# PCB-E21-TVS.net
KiCad netlist of a schematic drawn in EAGLE
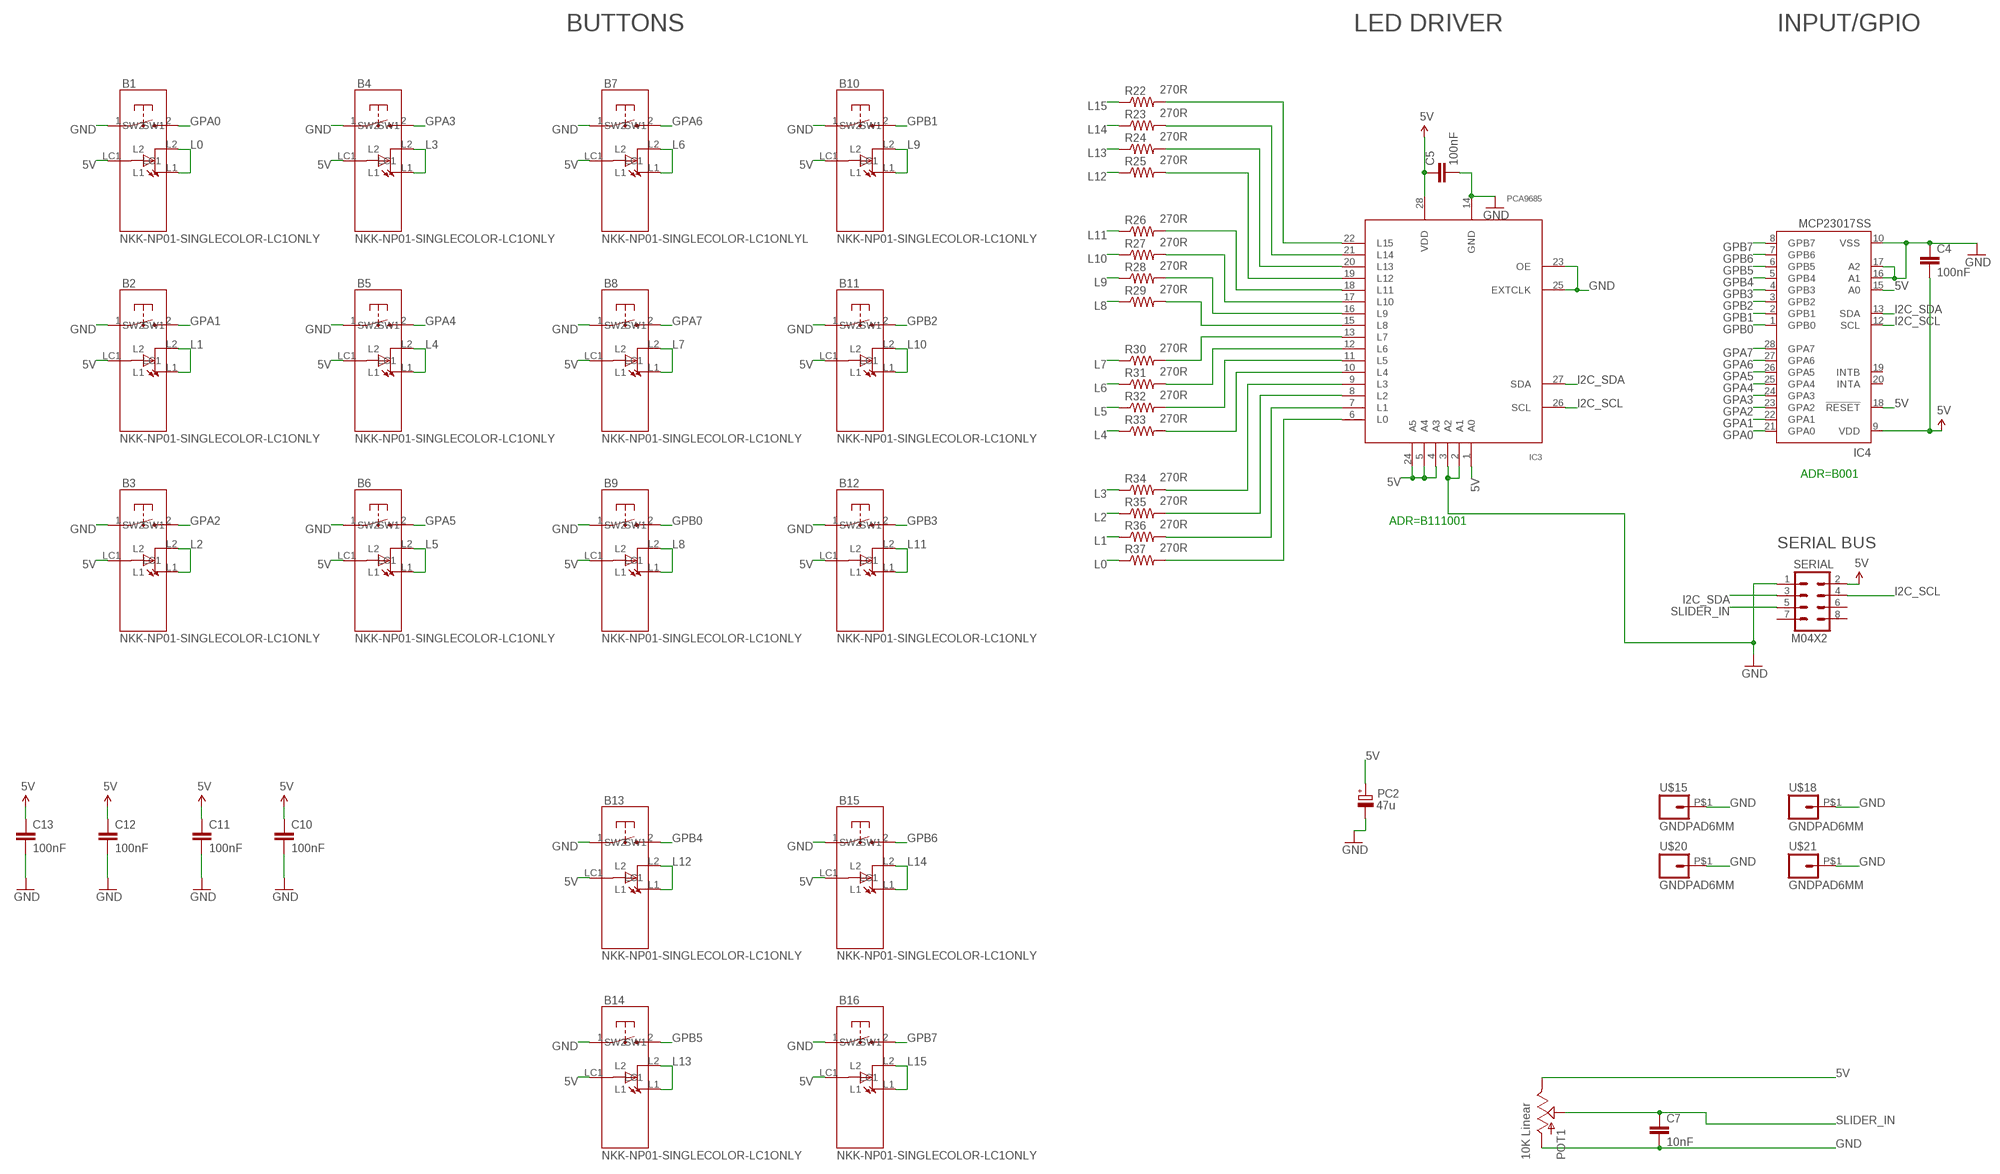
[diagram p0: schematic, sheet 1]

(export (version "E")
  (design (tool "Eeschema 10.0.6"))
  (components
    (comp (ref "B1")
      (value "NKK-NP01-SINGLECOLOR-LC1ONLY")
      (footprint "eagle-import:NKK-NP01_LESSHOLES2")
      (libsource (lib "eagle-import") (part "NKK-NP01-SINGLECOLOR-LC1ONLY"))
    )
    (comp (ref "B2")
      (value "NKK-NP01-SINGLECOLOR-LC1ONLY")
      (footprint "eagle-import:NKK-NP01_LESSHOLES2")
      (libsource (lib "eagle-import") (part "NKK-NP01-SINGLECOLOR-LC1ONLY"))
    )
    (comp (ref "B3")
      (value "NKK-NP01-SINGLECOLOR-LC1ONLY")
      (footprint "eagle-import:NKK-NP01_LESSHOLES2")
      (libsource (lib "eagle-import") (part "NKK-NP01-SINGLECOLOR-LC1ONLY"))
    )
    (comp (ref "B4")
      (value "NKK-NP01-SINGLECOLOR-LC1ONLY")
      (footprint "eagle-import:NKK-NP01_LESSHOLES2")
      (libsource (lib "eagle-import") (part "NKK-NP01-SINGLECOLOR-LC1ONLY"))
    )
    (comp (ref "B5")
      (value "NKK-NP01-SINGLECOLOR-LC1ONLY")
      (footprint "eagle-import:NKK-NP01_LESSHOLES2")
      (libsource (lib "eagle-import") (part "NKK-NP01-SINGLECOLOR-LC1ONLY"))
    )
    (comp (ref "B6")
      (value "NKK-NP01-SINGLECOLOR-LC1ONLY")
      (footprint "eagle-import:NKK-NP01_LESSHOLES2")
      (libsource (lib "eagle-import") (part "NKK-NP01-SINGLECOLOR-LC1ONLY"))
    )
    (comp (ref "B7")
      (value "NKK-NP01-SINGLECOLOR-LC1ONLYL")
      (footprint "eagle-import:NKK-NP01_LESSHOLES3")
      (libsource (lib "eagle-import") (part "NKK-NP01-SINGLECOLOR-LC1ONLYL"))
    )
    (comp (ref "B8")
      (value "NKK-NP01-SINGLECOLOR-LC1ONLY")
      (footprint "eagle-import:NKK-NP01_LESSHOLES2")
      (libsource (lib "eagle-import") (part "NKK-NP01-SINGLECOLOR-LC1ONLY"))
    )
    (comp (ref "B9")
      (value "NKK-NP01-SINGLECOLOR-LC1ONLY")
      (footprint "eagle-import:NKK-NP01_LESSHOLES2")
      (libsource (lib "eagle-import") (part "NKK-NP01-SINGLECOLOR-LC1ONLY"))
    )
    (comp (ref "B10")
      (value "NKK-NP01-SINGLECOLOR-LC1ONLY")
      (footprint "eagle-import:NKK-NP01_LESSHOLES2")
      (libsource (lib "eagle-import") (part "NKK-NP01-SINGLECOLOR-LC1ONLY"))
    )
    (comp (ref "B11")
      (value "NKK-NP01-SINGLECOLOR-LC1ONLY")
      (footprint "eagle-import:NKK-NP01_LESSHOLES2")
      (libsource (lib "eagle-import") (part "NKK-NP01-SINGLECOLOR-LC1ONLY"))
    )
    (comp (ref "B12")
      (value "NKK-NP01-SINGLECOLOR-LC1ONLY")
      (footprint "eagle-import:NKK-NP01_LESSHOLES2")
      (libsource (lib "eagle-import") (part "NKK-NP01-SINGLECOLOR-LC1ONLY"))
    )
    (comp (ref "B13")
      (value "NKK-NP01-SINGLECOLOR-LC1ONLY")
      (footprint "eagle-import:NKK-NP01_LESSHOLES2")
      (libsource (lib "eagle-import") (part "NKK-NP01-SINGLECOLOR-LC1ONLY"))
    )
    (comp (ref "B14")
      (value "NKK-NP01-SINGLECOLOR-LC1ONLY")
      (footprint "eagle-import:NKK-NP01_LESSHOLES2")
      (libsource (lib "eagle-import") (part "NKK-NP01-SINGLECOLOR-LC1ONLY"))
    )
    (comp (ref "B15")
      (value "NKK-NP01-SINGLECOLOR-LC1ONLY")
      (footprint "eagle-import:NKK-NP01_LESSHOLES2")
      (libsource (lib "eagle-import") (part "NKK-NP01-SINGLECOLOR-LC1ONLY"))
    )
    (comp (ref "B16")
      (value "NKK-NP01-SINGLECOLOR-LC1ONLY")
      (footprint "eagle-import:NKK-NP01_LESSHOLES2")
      (libsource (lib "eagle-import") (part "NKK-NP01-SINGLECOLOR-LC1ONLY"))
    )
    (comp (ref "C4")
      (value "100nF")
      (footprint "eagle-import:0603-CAP")
      (libsource (lib "eagle-import") (part "CAP0603-CAP"))
    )
    (comp (ref "C5")
      (value "100nF")
      (footprint "eagle-import:0603-CAP")
      (libsource (lib "eagle-import") (part "CAP0603-CAP"))
    )
    (comp (ref "C7")
      (value "10nF")
      (footprint "eagle-import:0603-CAP")
      (libsource (lib "eagle-import") (part "CAP0603-CAP"))
    )
    (comp (ref "C10")
      (value "100nF")
      (footprint "eagle-import:0603-CAP")
      (libsource (lib "eagle-import") (part "CAP0603-CAP"))
    )
    (comp (ref "C11")
      (value "100nF")
      (footprint "eagle-import:0603-CAP")
      (libsource (lib "eagle-import") (part "CAP0603-CAP"))
    )
    (comp (ref "C12")
      (value "100nF")
      (footprint "eagle-import:0603-CAP")
      (libsource (lib "eagle-import") (part "CAP0603-CAP"))
    )
    (comp (ref "C13")
      (value "100nF")
      (footprint "eagle-import:0603-CAP")
      (libsource (lib "eagle-import") (part "CAP0603-CAP"))
    )
    (comp (ref "IC3")
      (value "PCA9685")
      (footprint "eagle-import:TSSOP28")
      (libsource (lib "eagle-import") (part "PCA9685"))
    )
    (comp (ref "IC4")
      (value "MCP23017SS")
      (footprint "eagle-import:SSOP28")
      (fields
        (field (name "MF") "MICROCHIP")
        (field (name "MPN") "MCP23017-E/SS")
        (field (name "MPN_1") "MCP23017-E/SS")
        (field (name "OC_FARNELL") "1467674")
        (field (name "OC_NEWARK") "31K2960")
      )
      (libsource (lib "eagle-import") (part "MCP23017SS"))
    )
    (comp (ref "PC2")
      (value "47u")
      (footprint "eagle-import:PANASONIC_D")
      (libsource (lib "eagle-import") (part "CPOL-EUD"))
    )
    (comp (ref "POT1")
      (value "10K Linear")
      (footprint "eagle-import:SLIDER20-CAR2")
      (libsource (lib "eagle-import") (part "SLIDERC220"))
    )
    (comp (ref "R22")
      (value "270R")
      (footprint "eagle-import:0603-RES")
      (libsource (lib "eagle-import") (part "RESISTOR0603-RES"))
    )
    (comp (ref "R23")
      (value "270R")
      (footprint "eagle-import:0603-RES")
      (libsource (lib "eagle-import") (part "RESISTOR0603-RES"))
    )
    (comp (ref "R24")
      (value "270R")
      (footprint "eagle-import:0603-RES")
      (libsource (lib "eagle-import") (part "RESISTOR0603-RES"))
    )
    (comp (ref "R25")
      (value "270R")
      (footprint "eagle-import:0603-RES")
      (libsource (lib "eagle-import") (part "RESISTOR0603-RES"))
    )
    (comp (ref "R26")
      (value "270R")
      (footprint "eagle-import:0603-RES")
      (libsource (lib "eagle-import") (part "RESISTOR0603-RES"))
    )
    (comp (ref "R27")
      (value "270R")
      (footprint "eagle-import:0603-RES")
      (libsource (lib "eagle-import") (part "RESISTOR0603-RES"))
    )
    (comp (ref "R28")
      (value "270R")
      (footprint "eagle-import:0603-RES")
      (libsource (lib "eagle-import") (part "RESISTOR0603-RES"))
    )
    (comp (ref "R29")
      (value "270R")
      (footprint "eagle-import:0603-RES")
      (libsource (lib "eagle-import") (part "RESISTOR0603-RES"))
    )
    (comp (ref "R30")
      (value "270R")
      (footprint "eagle-import:0603-RES")
      (libsource (lib "eagle-import") (part "RESISTOR0603-RES"))
    )
    (comp (ref "R31")
      (value "270R")
      (footprint "eagle-import:0603-RES")
      (libsource (lib "eagle-import") (part "RESISTOR0603-RES"))
    )
    (comp (ref "R32")
      (value "270R")
      (footprint "eagle-import:0603-RES")
      (libsource (lib "eagle-import") (part "RESISTOR0603-RES"))
    )
    (comp (ref "R33")
      (value "270R")
      (footprint "eagle-import:0603-RES")
      (libsource (lib "eagle-import") (part "RESISTOR0603-RES"))
    )
    (comp (ref "R34")
      (value "270R")
      (footprint "eagle-import:0603-RES")
      (libsource (lib "eagle-import") (part "RESISTOR0603-RES"))
    )
    (comp (ref "R35")
      (value "270R")
      (footprint "eagle-import:0603-RES")
      (libsource (lib "eagle-import") (part "RESISTOR0603-RES"))
    )
    (comp (ref "R36")
      (value "270R")
      (footprint "eagle-import:0603-RES")
      (libsource (lib "eagle-import") (part "RESISTOR0603-RES"))
    )
    (comp (ref "R37")
      (value "270R")
      (footprint "eagle-import:0603-RES")
      (libsource (lib "eagle-import") (part "RESISTOR0603-RES"))
    )
    (comp (ref "SERIAL")
      (value "M04X2")
      (footprint "eagle-import:2X4")
      (libsource (lib "eagle-import") (part "M04X2"))
    )
    (comp (ref "U$15")
      (value "GNDPAD6MM")
      (footprint "eagle-import:3.2MMPAD6MM")
      (libsource (lib "eagle-import") (part "GNDPAD6MM"))
    )
    (comp (ref "U$18")
      (value "GNDPAD6MM")
      (footprint "eagle-import:3.2MMPAD6MM")
      (libsource (lib "eagle-import") (part "GNDPAD6MM"))
    )
    (comp (ref "U$20")
      (value "GNDPAD6MM")
      (footprint "eagle-import:3.2MMPAD6MM")
      (libsource (lib "eagle-import") (part "GNDPAD6MM"))
    )
    (comp (ref "U$21")
      (value "GNDPAD6MM")
      (footprint "eagle-import:3.2MMPAD6MM")
      (libsource (lib "eagle-import") (part "GNDPAD6MM"))
    )
  )
  (nets
    (net (code "1") (name "5V") (class "Default")
      (node (ref "B1") (pin "LC1") (pinfunction "LC1_LC1") (pintype "bidirectional"))
      (node (ref "B10") (pin "LC1") (pinfunction "LC1_LC1") (pintype "bidirectional"))
      (node (ref "B11") (pin "LC1") (pinfunction "LC1_LC1") (pintype "bidirectional"))
      (node (ref "B12") (pin "LC1") (pinfunction "LC1_LC1") (pintype "bidirectional"))
      (node (ref "B13") (pin "LC1") (pinfunction "LC1_LC1") (pintype "bidirectional"))
      (node (ref "B14") (pin "LC1") (pinfunction "LC1_LC1") (pintype "bidirectional"))
      (node (ref "B15") (pin "LC1") (pinfunction "LC1_LC1") (pintype "bidirectional"))
      (node (ref "B16") (pin "LC1") (pinfunction "LC1_LC1") (pintype "bidirectional"))
      (node (ref "B2") (pin "LC1") (pinfunction "LC1_LC1") (pintype "bidirectional"))
      (node (ref "B3") (pin "LC1") (pinfunction "LC1_LC1") (pintype "bidirectional"))
      (node (ref "B4") (pin "LC1") (pinfunction "LC1_LC1") (pintype "bidirectional"))
      (node (ref "B5") (pin "LC1") (pinfunction "LC1_LC1") (pintype "bidirectional"))
      (node (ref "B6") (pin "LC1") (pinfunction "LC1_LC1") (pintype "bidirectional"))
      (node (ref "B7") (pin "LC1") (pinfunction "LC1_LC1") (pintype "bidirectional"))
      (node (ref "B8") (pin "LC1") (pinfunction "LC1_LC1") (pintype "bidirectional"))
      (node (ref "B9") (pin "LC1") (pinfunction "LC1_LC1") (pintype "bidirectional"))
      (node (ref "C10") (pin "1") (pinfunction "1_1") (pintype "passive"))
      (node (ref "C11") (pin "1") (pinfunction "1_1") (pintype "passive"))
      (node (ref "C12") (pin "1") (pinfunction "1_1") (pintype "passive"))
      (node (ref "C13") (pin "1") (pinfunction "1_1") (pintype "passive"))
      (node (ref "C4") (pin "2") (pinfunction "2_2") (pintype "passive"))
      (node (ref "C5") (pin "1") (pinfunction "1_1") (pintype "passive"))
      (node (ref "IC3") (pin "1") (pinfunction "A0_1") (pintype "input"))
      (node (ref "IC3") (pin "24") (pinfunction "A5_24") (pintype "input"))
      (node (ref "IC3") (pin "28") (pinfunction "VDD_28") (pintype "power_in"))
      (node (ref "IC3") (pin "4") (pinfunction "A3_4") (pintype "input"))
      (node (ref "IC3") (pin "5") (pinfunction "A4_5") (pintype "input"))
      (node (ref "IC4") (pin "15") (pinfunction "A0_15") (pintype "input"))
      (node (ref "IC4") (pin "18") (pinfunction "~{RESET}_18") (pintype "input"))
      (node (ref "IC4") (pin "9") (pinfunction "VDD_9") (pintype "power_in"))
      (node (ref "PC2") (pin "+") (pinfunction "+_+") (pintype "passive"))
      (node (ref "POT1") (pin "1") (pinfunction "E_1") (pintype "passive"))
      (node (ref "SERIAL") (pin "2") (pinfunction "2_2") (pintype "passive"))
    )
    (net (code "2") (name "GND") (class "Default")
      (node (ref "B1") (pin "1") (pinfunction "SW1_1") (pintype "bidirectional"))
      (node (ref "B10") (pin "1") (pinfunction "SW1_1") (pintype "bidirectional"))
      (node (ref "B11") (pin "1") (pinfunction "SW1_1") (pintype "bidirectional"))
      (node (ref "B12") (pin "1") (pinfunction "SW1_1") (pintype "bidirectional"))
      (node (ref "B13") (pin "1") (pinfunction "SW1_1") (pintype "bidirectional"))
      (node (ref "B14") (pin "1") (pinfunction "SW1_1") (pintype "bidirectional"))
      (node (ref "B15") (pin "1") (pinfunction "SW1_1") (pintype "bidirectional"))
      (node (ref "B16") (pin "1") (pinfunction "SW1_1") (pintype "bidirectional"))
      (node (ref "B2") (pin "1") (pinfunction "SW1_1") (pintype "bidirectional"))
      (node (ref "B3") (pin "1") (pinfunction "SW1_1") (pintype "bidirectional"))
      (node (ref "B4") (pin "1") (pinfunction "SW1_1") (pintype "bidirectional"))
      (node (ref "B5") (pin "1") (pinfunction "SW1_1") (pintype "bidirectional"))
      (node (ref "B6") (pin "1") (pinfunction "SW1_1") (pintype "bidirectional"))
      (node (ref "B7") (pin "1") (pinfunction "SW1_1") (pintype "bidirectional"))
      (node (ref "B8") (pin "1") (pinfunction "SW1_1") (pintype "bidirectional"))
      (node (ref "B9") (pin "1") (pinfunction "SW1_1") (pintype "bidirectional"))
      (node (ref "C10") (pin "2") (pinfunction "2_2") (pintype "passive"))
      (node (ref "C11") (pin "2") (pinfunction "2_2") (pintype "passive"))
      (node (ref "C12") (pin "2") (pinfunction "2_2") (pintype "passive"))
      (node (ref "C13") (pin "2") (pinfunction "2_2") (pintype "passive"))
      (node (ref "C4") (pin "1") (pinfunction "1_1") (pintype "passive"))
      (node (ref "C5") (pin "2") (pinfunction "2_2") (pintype "passive"))
      (node (ref "C7") (pin "2") (pinfunction "2_2") (pintype "passive"))
      (node (ref "IC3") (pin "14") (pinfunction "GND_14") (pintype "power_in"))
      (node (ref "IC3") (pin "2") (pinfunction "A1_2") (pintype "input"))
      (node (ref "IC3") (pin "23") (pinfunction "OE_23") (pintype "input"))
      (node (ref "IC3") (pin "25") (pinfunction "EXTCLK_25") (pintype "input"))
      (node (ref "IC3") (pin "3") (pinfunction "A2_3") (pintype "input"))
      (node (ref "IC4") (pin "10") (pinfunction "VSS_10") (pintype "power_in"))
      (node (ref "IC4") (pin "16") (pinfunction "A1_16") (pintype "input"))
      (node (ref "IC4") (pin "17") (pinfunction "A2_17") (pintype "input"))
      (node (ref "PC2") (pin "-") (pinfunction "-_-") (pintype "passive"))
      (node (ref "POT1") (pin "3") (pinfunction "A_3") (pintype "passive"))
      (node (ref "SERIAL") (pin "1") (pinfunction "1_1") (pintype "passive"))
      (node (ref "U$15") (pin "P$1") (pinfunction "1_P$1") (pintype "passive"))
      (node (ref "U$18") (pin "P$1") (pinfunction "1_P$1") (pintype "passive"))
      (node (ref "U$20") (pin "P$1") (pinfunction "1_P$1") (pintype "passive"))
      (node (ref "U$21") (pin "P$1") (pinfunction "1_P$1") (pintype "passive"))
    )
    (net (code "3") (name "GPA0") (class "Default")
      (node (ref "B1") (pin "2") (pinfunction "SW2_2") (pintype "bidirectional"))
      (node (ref "IC4") (pin "21") (pinfunction "GPA0_21") (pintype "bidirectional"))
    )
    (net (code "4") (name "GPA1") (class "Default")
      (node (ref "B2") (pin "2") (pinfunction "SW2_2") (pintype "bidirectional"))
      (node (ref "IC4") (pin "22") (pinfunction "GPA1_22") (pintype "bidirectional"))
    )
    (net (code "5") (name "GPA2") (class "Default")
      (node (ref "B3") (pin "2") (pinfunction "SW2_2") (pintype "bidirectional"))
      (node (ref "IC4") (pin "23") (pinfunction "GPA2_23") (pintype "bidirectional"))
    )
    (net (code "6") (name "GPA3") (class "Default")
      (node (ref "B4") (pin "2") (pinfunction "SW2_2") (pintype "bidirectional"))
      (node (ref "IC4") (pin "24") (pinfunction "GPA3_24") (pintype "bidirectional"))
    )
    (net (code "7") (name "GPA4") (class "Default")
      (node (ref "B5") (pin "2") (pinfunction "SW2_2") (pintype "bidirectional"))
      (node (ref "IC4") (pin "25") (pinfunction "GPA4_25") (pintype "bidirectional"))
    )
    (net (code "8") (name "GPA5") (class "Default")
      (node (ref "B6") (pin "2") (pinfunction "SW2_2") (pintype "bidirectional"))
      (node (ref "IC4") (pin "26") (pinfunction "GPA5_26") (pintype "bidirectional"))
    )
    (net (code "9") (name "GPA6") (class "Default")
      (node (ref "B7") (pin "2") (pinfunction "SW2_2") (pintype "bidirectional"))
      (node (ref "IC4") (pin "27") (pinfunction "GPA6_27") (pintype "bidirectional"))
    )
    (net (code "10") (name "GPA7") (class "Default")
      (node (ref "B8") (pin "2") (pinfunction "SW2_2") (pintype "bidirectional"))
      (node (ref "IC4") (pin "28") (pinfunction "GPA7_28") (pintype "bidirectional"))
    )
    (net (code "11") (name "GPB0") (class "Default")
      (node (ref "B9") (pin "2") (pinfunction "SW2_2") (pintype "bidirectional"))
      (node (ref "IC4") (pin "1") (pinfunction "GPB0_1") (pintype "bidirectional"))
    )
    (net (code "12") (name "GPB1") (class "Default")
      (node (ref "B10") (pin "2") (pinfunction "SW2_2") (pintype "bidirectional"))
      (node (ref "IC4") (pin "2") (pinfunction "GPB1_2") (pintype "bidirectional"))
    )
    (net (code "13") (name "GPB2") (class "Default")
      (node (ref "B11") (pin "2") (pinfunction "SW2_2") (pintype "bidirectional"))
      (node (ref "IC4") (pin "3") (pinfunction "GPB2_3") (pintype "bidirectional"))
    )
    (net (code "14") (name "GPB3") (class "Default")
      (node (ref "B12") (pin "2") (pinfunction "SW2_2") (pintype "bidirectional"))
      (node (ref "IC4") (pin "4") (pinfunction "GPB3_4") (pintype "bidirectional"))
    )
    (net (code "15") (name "GPB4") (class "Default")
      (node (ref "B13") (pin "2") (pinfunction "SW2_2") (pintype "bidirectional"))
      (node (ref "IC4") (pin "5") (pinfunction "GPB4_5") (pintype "bidirectional"))
    )
    (net (code "16") (name "GPB5") (class "Default")
      (node (ref "B14") (pin "2") (pinfunction "SW2_2") (pintype "bidirectional"))
      (node (ref "IC4") (pin "6") (pinfunction "GPB5_6") (pintype "bidirectional"))
    )
    (net (code "17") (name "GPB6") (class "Default")
      (node (ref "B15") (pin "2") (pinfunction "SW2_2") (pintype "bidirectional"))
      (node (ref "IC4") (pin "7") (pinfunction "GPB6_7") (pintype "bidirectional"))
    )
    (net (code "18") (name "GPB7") (class "Default")
      (node (ref "B16") (pin "2") (pinfunction "SW2_2") (pintype "bidirectional"))
      (node (ref "IC4") (pin "8") (pinfunction "GPB7_8") (pintype "bidirectional"))
    )
    (net (code "19") (name "I2C_SCL") (class "Default")
      (node (ref "IC3") (pin "26") (pinfunction "SCL_26") (pintype "input"))
      (node (ref "IC4") (pin "12") (pinfunction "SCL_12") (pintype "input"))
      (node (ref "SERIAL") (pin "4") (pinfunction "4_4") (pintype "passive"))
    )
    (net (code "20") (name "I2C_SDA") (class "Default")
      (node (ref "IC3") (pin "27") (pinfunction "SDA_27") (pintype "input"))
      (node (ref "IC4") (pin "13") (pinfunction "SDA_13") (pintype "bidirectional"))
      (node (ref "SERIAL") (pin "3") (pinfunction "3_3") (pintype "passive"))
    )
    (net (code "21") (name "L0") (class "Default")
      (node (ref "B1") (pin "L1") (pinfunction "L1_L1") (pintype "bidirectional"))
      (node (ref "B1") (pin "L2") (pinfunction "L2_L2") (pintype "bidirectional"))
      (node (ref "R37") (pin "1") (pinfunction "1_1") (pintype "passive"))
    )
    (net (code "22") (name "L1") (class "Default")
      (node (ref "B2") (pin "L1") (pinfunction "L1_L1") (pintype "bidirectional"))
      (node (ref "B2") (pin "L2") (pinfunction "L2_L2") (pintype "bidirectional"))
      (node (ref "R36") (pin "1") (pinfunction "1_1") (pintype "passive"))
    )
    (net (code "23") (name "L2") (class "Default")
      (node (ref "B3") (pin "L1") (pinfunction "L1_L1") (pintype "bidirectional"))
      (node (ref "B3") (pin "L2") (pinfunction "L2_L2") (pintype "bidirectional"))
      (node (ref "R35") (pin "1") (pinfunction "1_1") (pintype "passive"))
    )
    (net (code "24") (name "L3") (class "Default")
      (node (ref "B4") (pin "L1") (pinfunction "L1_L1") (pintype "bidirectional"))
      (node (ref "B4") (pin "L2") (pinfunction "L2_L2") (pintype "bidirectional"))
      (node (ref "R34") (pin "1") (pinfunction "1_1") (pintype "passive"))
    )
    (net (code "25") (name "L4") (class "Default")
      (node (ref "B5") (pin "L1") (pinfunction "L1_L1") (pintype "bidirectional"))
      (node (ref "B5") (pin "L2") (pinfunction "L2_L2") (pintype "bidirectional"))
      (node (ref "R33") (pin "1") (pinfunction "1_1") (pintype "passive"))
    )
    (net (code "26") (name "L5") (class "Default")
      (node (ref "B6") (pin "L1") (pinfunction "L1_L1") (pintype "bidirectional"))
      (node (ref "B6") (pin "L2") (pinfunction "L2_L2") (pintype "bidirectional"))
      (node (ref "R32") (pin "1") (pinfunction "1_1") (pintype "passive"))
    )
    (net (code "27") (name "L6") (class "Default")
      (node (ref "B7") (pin "L1") (pinfunction "L1_L1") (pintype "bidirectional"))
      (node (ref "B7") (pin "L2") (pinfunction "L2_L2") (pintype "bidirectional"))
      (node (ref "R31") (pin "1") (pinfunction "1_1") (pintype "passive"))
    )
    (net (code "28") (name "L7") (class "Default")
      (node (ref "B8") (pin "L1") (pinfunction "L1_L1") (pintype "bidirectional"))
      (node (ref "B8") (pin "L2") (pinfunction "L2_L2") (pintype "bidirectional"))
      (node (ref "R30") (pin "1") (pinfunction "1_1") (pintype "passive"))
    )
    (net (code "29") (name "L8") (class "Default")
      (node (ref "B9") (pin "L1") (pinfunction "L1_L1") (pintype "bidirectional"))
      (node (ref "B9") (pin "L2") (pinfunction "L2_L2") (pintype "bidirectional"))
      (node (ref "R29") (pin "1") (pinfunction "1_1") (pintype "passive"))
    )
    (net (code "30") (name "L9") (class "Default")
      (node (ref "B10") (pin "L1") (pinfunction "L1_L1") (pintype "bidirectional"))
      (node (ref "B10") (pin "L2") (pinfunction "L2_L2") (pintype "bidirectional"))
      (node (ref "R28") (pin "1") (pinfunction "1_1") (pintype "passive"))
    )
    (net (code "31") (name "L10") (class "Default")
      (node (ref "B11") (pin "L1") (pinfunction "L1_L1") (pintype "bidirectional"))
      (node (ref "B11") (pin "L2") (pinfunction "L2_L2") (pintype "bidirectional"))
      (node (ref "R27") (pin "1") (pinfunction "1_1") (pintype "passive"))
    )
    (net (code "32") (name "L11") (class "Default")
      (node (ref "B12") (pin "L1") (pinfunction "L1_L1") (pintype "bidirectional"))
      (node (ref "B12") (pin "L2") (pinfunction "L2_L2") (pintype "bidirectional"))
      (node (ref "R26") (pin "1") (pinfunction "1_1") (pintype "passive"))
    )
    (net (code "33") (name "L12") (class "Default")
      (node (ref "B13") (pin "L1") (pinfunction "L1_L1") (pintype "bidirectional"))
      (node (ref "B13") (pin "L2") (pinfunction "L2_L2") (pintype "bidirectional"))
      (node (ref "R25") (pin "1") (pinfunction "1_1") (pintype "passive"))
    )
    (net (code "34") (name "L13") (class "Default")
      (node (ref "B14") (pin "L1") (pinfunction "L1_L1") (pintype "bidirectional"))
      (node (ref "B14") (pin "L2") (pinfunction "L2_L2") (pintype "bidirectional"))
      (node (ref "R24") (pin "1") (pinfunction "1_1") (pintype "passive"))
    )
    (net (code "35") (name "L14") (class "Default")
      (node (ref "B15") (pin "L1") (pinfunction "L1_L1") (pintype "bidirectional"))
      (node (ref "B15") (pin "L2") (pinfunction "L2_L2") (pintype "bidirectional"))
      (node (ref "R23") (pin "1") (pinfunction "1_1") (pintype "passive"))
    )
    (net (code "36") (name "L15") (class "Default")
      (node (ref "B16") (pin "L1") (pinfunction "L1_L1") (pintype "bidirectional"))
      (node (ref "B16") (pin "L2") (pinfunction "L2_L2") (pintype "bidirectional"))
      (node (ref "R22") (pin "1") (pinfunction "1_1") (pintype "passive"))
    )
    (net (code "37") (name "Net-(IC3-L0)") (class "Default")
      (node (ref "IC3") (pin "6") (pinfunction "L0_6") (pintype "output"))
      (node (ref "R37") (pin "2") (pinfunction "2_2") (pintype "passive"))
    )
    (net (code "38") (name "Net-(IC3-L1)") (class "Default")
      (node (ref "IC3") (pin "7") (pinfunction "L1_7") (pintype "output"))
      (node (ref "R36") (pin "2") (pinfunction "2_2") (pintype "passive"))
    )
    (net (code "39") (name "Net-(IC3-L2)") (class "Default")
      (node (ref "IC3") (pin "8") (pinfunction "L2_8") (pintype "output"))
      (node (ref "R35") (pin "2") (pinfunction "2_2") (pintype "passive"))
    )
    (net (code "40") (name "Net-(IC3-L3)") (class "Default")
      (node (ref "IC3") (pin "9") (pinfunction "L3_9") (pintype "output"))
      (node (ref "R34") (pin "2") (pinfunction "2_2") (pintype "passive"))
    )
    (net (code "41") (name "Net-(IC3-L4)") (class "Default")
      (node (ref "IC3") (pin "10") (pinfunction "L4_10") (pintype "output"))
      (node (ref "R33") (pin "2") (pinfunction "2_2") (pintype "passive"))
    )
    (net (code "42") (name "Net-(IC3-L5)") (class "Default")
      (node (ref "IC3") (pin "11") (pinfunction "L5_11") (pintype "output"))
      (node (ref "R32") (pin "2") (pinfunction "2_2") (pintype "passive"))
    )
    (net (code "43") (name "Net-(IC3-L6)") (class "Default")
      (node (ref "IC3") (pin "12") (pinfunction "L6_12") (pintype "output"))
      (node (ref "R31") (pin "2") (pinfunction "2_2") (pintype "passive"))
    )
    (net (code "44") (name "Net-(IC3-L7)") (class "Default")
      (node (ref "IC3") (pin "13") (pinfunction "L7_13") (pintype "output"))
      (node (ref "R30") (pin "2") (pinfunction "2_2") (pintype "passive"))
    )
    (net (code "45") (name "Net-(IC3-L8)") (class "Default")
      (node (ref "IC3") (pin "15") (pinfunction "L8_15") (pintype "output"))
      (node (ref "R29") (pin "2") (pinfunction "2_2") (pintype "passive"))
    )
    (net (code "46") (name "Net-(IC3-L9)") (class "Default")
      (node (ref "IC3") (pin "16") (pinfunction "L9_16") (pintype "output"))
      (node (ref "R28") (pin "2") (pinfunction "2_2") (pintype "passive"))
    )
    (net (code "47") (name "Net-(IC3-L10)") (class "Default")
      (node (ref "IC3") (pin "17") (pinfunction "L10_17") (pintype "output"))
      (node (ref "R27") (pin "2") (pinfunction "2_2") (pintype "passive"))
    )
    (net (code "48") (name "Net-(IC3-L11)") (class "Default")
      (node (ref "IC3") (pin "18") (pinfunction "L11_18") (pintype "output"))
      (node (ref "R26") (pin "2") (pinfunction "2_2") (pintype "passive"))
    )
    (net (code "49") (name "Net-(IC3-L12)") (class "Default")
      (node (ref "IC3") (pin "19") (pinfunction "L12_19") (pintype "output"))
      (node (ref "R25") (pin "2") (pinfunction "2_2") (pintype "passive"))
    )
    (net (code "50") (name "Net-(IC3-L13)") (class "Default")
      (node (ref "IC3") (pin "20") (pinfunction "L13_20") (pintype "output"))
      (node (ref "R24") (pin "2") (pinfunction "2_2") (pintype "passive"))
    )
    (net (code "51") (name "Net-(IC3-L14)") (class "Default")
      (node (ref "IC3") (pin "21") (pinfunction "L14_21") (pintype "output"))
      (node (ref "R23") (pin "2") (pinfunction "2_2") (pintype "passive"))
    )
    (net (code "52") (name "Net-(IC3-L15)") (class "Default")
      (node (ref "IC3") (pin "22") (pinfunction "L15_22") (pintype "output"))
      (node (ref "R22") (pin "2") (pinfunction "2_2") (pintype "passive"))
    )
    (net (code "53") (name "SLIDER_IN") (class "Default")
      (node (ref "C7") (pin "1") (pinfunction "1_1") (pintype "passive"))
      (node (ref "POT1") (pin "2A") (pinfunction "S_2A") (pintype "passive"))
      (node (ref "SERIAL") (pin "5") (pinfunction "5_5") (pintype "passive"))
    )
    (net (code "54") (name "unconnected-(IC4-INTA-Pad20)") (class "Default")
      (node (ref "IC4") (pin "20") (pinfunction "INTA_20") (pintype "output"))
    )
    (net (code "55") (name "unconnected-(IC4-INTB-Pad19)") (class "Default")
      (node (ref "IC4") (pin "19") (pinfunction "INTB_19") (pintype "output"))
    )
    (net (code "56") (name "unconnected-(SERIAL-Pad6)") (class "Default")
      (node (ref "SERIAL") (pin "6") (pinfunction "6_6") (pintype "passive"))
    )
    (net (code "57") (name "unconnected-(SERIAL-Pad7)") (class "Default")
      (node (ref "SERIAL") (pin "7") (pinfunction "7_7") (pintype "passive"))
    )
    (net (code "58") (name "unconnected-(SERIAL-Pad8)") (class "Default")
      (node (ref "SERIAL") (pin "8") (pinfunction "8_8") (pintype "passive"))
    )
  )
)
